# SouthSide.net
KiCad netlist of a schematic drawn in Altium Designer
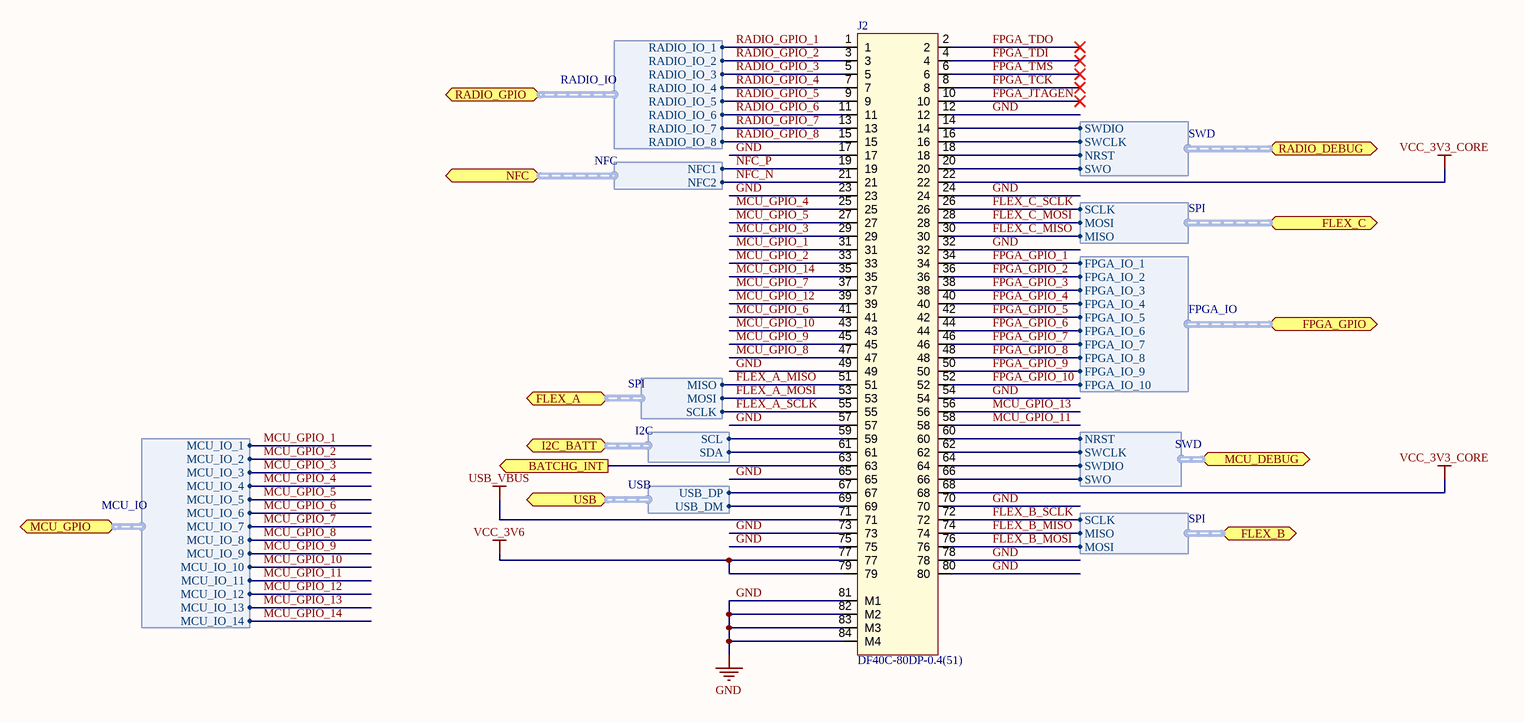
[diagram p0: SouthSide.SchDoc]

(export (version "E")
  (design (tool "Eeschema 10.0.6"))
  (components
    (comp (ref "J2")
      (value "DF40C-80DP-0.4(51)")
      (footprint "con80_hirose-df40c-80dp_129h")
      (description "CONN HDR 80POS 0.4MM SMD GOLD")
      (fields (field (name "MFG") "Hirose") (field (name "VOLTAGE") "30"))
      (libsource (lib "SynapseLibrary") (part "DF40C-80DP-0.4(51)"))
    )
  )
  (nets
    (net (code "9") (name "/BATCHG_INT") (class "Default")
      (node (ref "J2") (pin "63") (pinfunction "63_63") (pintype "passive"))
    )
    (net (code "10") (name "/FLEX_A_MISO") (class "Default")
      (node (ref "J2") (pin "51") (pinfunction "51_51") (pintype "passive"))
    )
    (net (code "11") (name "/FLEX_A_MOSI") (class "Default")
      (node (ref "J2") (pin "53") (pinfunction "53_53") (pintype "passive"))
    )
    (net (code "12") (name "/FLEX_A_SCLK") (class "Default")
      (node (ref "J2") (pin "55") (pinfunction "55_55") (pintype "passive"))
    )
    (net (code "13") (name "/FLEX_B_MISO") (class "Default")
      (node (ref "J2") (pin "74") (pinfunction "74_74") (pintype "passive"))
    )
    (net (code "14") (name "/FLEX_B_MOSI") (class "Default")
      (node (ref "J2") (pin "76") (pinfunction "76_76") (pintype "passive"))
    )
    (net (code "15") (name "/FLEX_B_SCLK") (class "Default")
      (node (ref "J2") (pin "72") (pinfunction "72_72") (pintype "passive"))
    )
    (net (code "16") (name "/FLEX_C_MISO") (class "Default")
      (node (ref "J2") (pin "30") (pinfunction "30_30") (pintype "passive"))
    )
    (net (code "17") (name "/FLEX_C_MOSI") (class "Default")
      (node (ref "J2") (pin "28") (pinfunction "28_28") (pintype "passive"))
    )
    (net (code "18") (name "/FLEX_C_SCLK") (class "Default")
      (node (ref "J2") (pin "26") (pinfunction "26_26") (pintype "passive"))
    )
    (net (code "19") (name "/FPGA_GPIO_1") (class "Default")
      (node (ref "J2") (pin "34") (pinfunction "34_34") (pintype "passive"))
    )
    (net (code "20") (name "/FPGA_GPIO_2") (class "Default")
      (node (ref "J2") (pin "36") (pinfunction "36_36") (pintype "passive"))
    )
    (net (code "21") (name "/FPGA_GPIO_3") (class "Default")
      (node (ref "J2") (pin "38") (pinfunction "38_38") (pintype "passive"))
    )
    (net (code "22") (name "/FPGA_GPIO_4") (class "Default")
      (node (ref "J2") (pin "40") (pinfunction "40_40") (pintype "passive"))
    )
    (net (code "23") (name "/FPGA_GPIO_5") (class "Default")
      (node (ref "J2") (pin "42") (pinfunction "42_42") (pintype "passive"))
    )
    (net (code "24") (name "/FPGA_GPIO_6") (class "Default")
      (node (ref "J2") (pin "44") (pinfunction "44_44") (pintype "passive"))
    )
    (net (code "25") (name "/FPGA_GPIO_7") (class "Default")
      (node (ref "J2") (pin "46") (pinfunction "46_46") (pintype "passive"))
    )
    (net (code "26") (name "/FPGA_GPIO_8") (class "Default")
      (node (ref "J2") (pin "48") (pinfunction "48_48") (pintype "passive"))
    )
    (net (code "27") (name "/FPGA_GPIO_9") (class "Default")
      (node (ref "J2") (pin "50") (pinfunction "50_50") (pintype "passive"))
    )
    (net (code "28") (name "/FPGA_GPIO_10") (class "Default")
      (node (ref "J2") (pin "52") (pinfunction "52_52") (pintype "passive"))
    )
    (net (code "29") (name "/FPGA_JTAGEN") (class "Default")
      (node (ref "J2") (pin "10") (pinfunction "10_10") (pintype "passive+no_connect"))
    )
    (net (code "30") (name "/FPGA_TCK") (class "Default")
      (node (ref "J2") (pin "8") (pinfunction "8_8") (pintype "passive+no_connect"))
    )
    (net (code "31") (name "/FPGA_TDI") (class "Default")
      (node (ref "J2") (pin "4") (pinfunction "4_4") (pintype "passive+no_connect"))
    )
    (net (code "32") (name "/FPGA_TDO") (class "Default")
      (node (ref "J2") (pin "2") (pinfunction "2_2") (pintype "passive+no_connect"))
    )
    (net (code "33") (name "/FPGA_TMS") (class "Default")
      (node (ref "J2") (pin "6") (pinfunction "6_6") (pintype "passive+no_connect"))
    )
    (net (code "34") (name "/MCU_GPIO_1") (class "Default")
      (node (ref "J2") (pin "31") (pinfunction "31_31") (pintype "passive"))
    )
    (net (code "35") (name "/MCU_GPIO_2") (class "Default")
      (node (ref "J2") (pin "33") (pinfunction "33_33") (pintype "passive"))
    )
    (net (code "36") (name "/MCU_GPIO_3") (class "Default")
      (node (ref "J2") (pin "29") (pinfunction "29_29") (pintype "passive"))
    )
    (net (code "37") (name "/MCU_GPIO_4") (class "Default")
      (node (ref "J2") (pin "25") (pinfunction "25_25") (pintype "passive"))
    )
    (net (code "38") (name "/MCU_GPIO_5") (class "Default")
      (node (ref "J2") (pin "27") (pinfunction "27_27") (pintype "passive"))
    )
    (net (code "39") (name "/MCU_GPIO_6") (class "Default")
      (node (ref "J2") (pin "41") (pinfunction "41_41") (pintype "passive"))
    )
    (net (code "40") (name "/MCU_GPIO_7") (class "Default")
      (node (ref "J2") (pin "37") (pinfunction "37_37") (pintype "passive"))
    )
    (net (code "41") (name "/MCU_GPIO_8") (class "Default")
      (node (ref "J2") (pin "47") (pinfunction "47_47") (pintype "passive"))
    )
    (net (code "42") (name "/MCU_GPIO_9") (class "Default")
      (node (ref "J2") (pin "45") (pinfunction "45_45") (pintype "passive"))
    )
    (net (code "43") (name "/MCU_GPIO_10") (class "Default")
      (node (ref "J2") (pin "43") (pinfunction "43_43") (pintype "passive"))
    )
    (net (code "44") (name "/MCU_GPIO_11") (class "Default")
      (node (ref "J2") (pin "58") (pinfunction "58_58") (pintype "passive"))
    )
    (net (code "45") (name "/MCU_GPIO_12") (class "Default")
      (node (ref "J2") (pin "39") (pinfunction "39_39") (pintype "passive"))
    )
    (net (code "46") (name "/MCU_GPIO_13") (class "Default")
      (node (ref "J2") (pin "56") (pinfunction "56_56") (pintype "passive"))
    )
    (net (code "47") (name "/MCU_GPIO_14") (class "Default")
      (node (ref "J2") (pin "35") (pinfunction "35_35") (pintype "passive"))
    )
    (net (code "48") (name "/NFC_N") (class "Default")
      (node (ref "J2") (pin "21") (pinfunction "21_21") (pintype "passive"))
    )
    (net (code "49") (name "/NFC_P") (class "Default")
      (node (ref "J2") (pin "19") (pinfunction "19_19") (pintype "passive"))
    )
    (net (code "50") (name "/RADIO_GPIO_1") (class "Default")
      (node (ref "J2") (pin "1") (pinfunction "1_1") (pintype "passive"))
    )
    (net (code "51") (name "/RADIO_GPIO_2") (class "Default")
      (node (ref "J2") (pin "3") (pinfunction "3_3") (pintype "passive"))
    )
    (net (code "52") (name "/RADIO_GPIO_3") (class "Default")
      (node (ref "J2") (pin "5") (pinfunction "5_5") (pintype "passive"))
    )
    (net (code "53") (name "/RADIO_GPIO_4") (class "Default")
      (node (ref "J2") (pin "7") (pinfunction "7_7") (pintype "passive"))
    )
    (net (code "54") (name "/RADIO_GPIO_5") (class "Default")
      (node (ref "J2") (pin "9") (pinfunction "9_9") (pintype "passive"))
    )
    (net (code "55") (name "/RADIO_GPIO_6") (class "Default")
      (node (ref "J2") (pin "11") (pinfunction "11_11") (pintype "passive"))
    )
    (net (code "56") (name "/RADIO_GPIO_7") (class "Default")
      (node (ref "J2") (pin "13") (pinfunction "13_13") (pintype "passive"))
    )
    (net (code "57") (name "/RADIO_GPIO_8") (class "Default")
      (node (ref "J2") (pin "15") (pinfunction "15_15") (pintype "passive"))
    )
    (net (code "58") (name "/SCL") (class "Default")
      (node (ref "J2") (pin "59") (pinfunction "59_59") (pintype "passive"))
    )
    (net (code "59") (name "/SDA") (class "Default")
      (node (ref "J2") (pin "61") (pinfunction "61_61") (pintype "passive"))
    )
    (net (code "60") (name "/USB_DM") (class "Default")
      (node (ref "J2") (pin "69") (pinfunction "69_69") (pintype "passive"))
    )
    (net (code "61") (name "/USB_DP") (class "Default")
      (node (ref "J2") (pin "67") (pinfunction "67_67") (pintype "passive"))
    )
    (net (code "70") (name "GND") (class "Default")
      (node (ref "J2") (pin "12") (pinfunction "12_12") (pintype "passive"))
      (node (ref "J2") (pin "17") (pinfunction "17_17") (pintype "passive"))
      (node (ref "J2") (pin "23") (pinfunction "23_23") (pintype "passive"))
      (node (ref "J2") (pin "24") (pinfunction "24_24") (pintype "passive"))
      (node (ref "J2") (pin "32") (pinfunction "32_32") (pintype "passive"))
      (node (ref "J2") (pin "49") (pinfunction "49_49") (pintype "passive"))
      (node (ref "J2") (pin "54") (pinfunction "54_54") (pintype "passive"))
      (node (ref "J2") (pin "57") (pinfunction "57_57") (pintype "passive"))
      (node (ref "J2") (pin "65") (pinfunction "65_65") (pintype "passive"))
      (node (ref "J2") (pin "70") (pinfunction "70_70") (pintype "passive"))
      (node (ref "J2") (pin "73") (pinfunction "73_73") (pintype "passive"))
      (node (ref "J2") (pin "75") (pinfunction "75_75") (pintype "passive"))
      (node (ref "J2") (pin "78") (pinfunction "78_78") (pintype "passive"))
      (node (ref "J2") (pin "80") (pinfunction "80_80") (pintype "passive"))
      (node (ref "J2") (pin "81") (pinfunction "M1_81") (pintype "passive"))
      (node (ref "J2") (pin "82") (pinfunction "M2_82") (pintype "passive"))
      (node (ref "J2") (pin "83") (pinfunction "M3_83") (pintype "passive"))
      (node (ref "J2") (pin "84") (pinfunction "M4_84") (pintype "passive"))
    )
    (net (code "71") (name "USB_VBUS") (class "Default")
      (node (ref "J2") (pin "71") (pinfunction "71_71") (pintype "passive"))
    )
    (net (code "72") (name "VCC_3V3_CORE") (class "Default")
      (node (ref "J2") (pin "22") (pinfunction "22_22") (pintype "passive"))
      (node (ref "J2") (pin "68") (pinfunction "68_68") (pintype "passive"))
    )
    (net (code "73") (name "VCC_3V6") (class "Default")
      (node (ref "J2") (pin "77") (pinfunction "77_77") (pintype "passive"))
      (node (ref "J2") (pin "79") (pinfunction "79_79") (pintype "passive"))
    )
    (net (code "74") (name "unconnected-(J2-Pad14)") (class "Default")
      (node (ref "J2") (pin "14") (pinfunction "14_14") (pintype "passive"))
    )
    (net (code "75") (name "unconnected-(J2-Pad16)") (class "Default")
      (node (ref "J2") (pin "16") (pinfunction "16_16") (pintype "passive"))
    )
    (net (code "76") (name "unconnected-(J2-Pad18)") (class "Default")
      (node (ref "J2") (pin "18") (pinfunction "18_18") (pintype "passive"))
    )
    (net (code "77") (name "unconnected-(J2-Pad20)") (class "Default")
      (node (ref "J2") (pin "20") (pinfunction "20_20") (pintype "passive"))
    )
    (net (code "78") (name "unconnected-(J2-Pad60)") (class "Default")
      (node (ref "J2") (pin "60") (pinfunction "60_60") (pintype "passive"))
    )
    (net (code "79") (name "unconnected-(J2-Pad62)") (class "Default")
      (node (ref "J2") (pin "62") (pinfunction "62_62") (pintype "passive"))
    )
    (net (code "80") (name "unconnected-(J2-Pad64)") (class "Default")
      (node (ref "J2") (pin "64") (pinfunction "64_64") (pintype "passive"))
    )
    (net (code "81") (name "unconnected-(J2-Pad66)") (class "Default")
      (node (ref "J2") (pin "66") (pinfunction "66_66") (pintype "passive"))
    )
  )
)
